# Weather_Station_v2_2-wihtparts.net
KiCad netlist of a schematic drawn in EAGLE
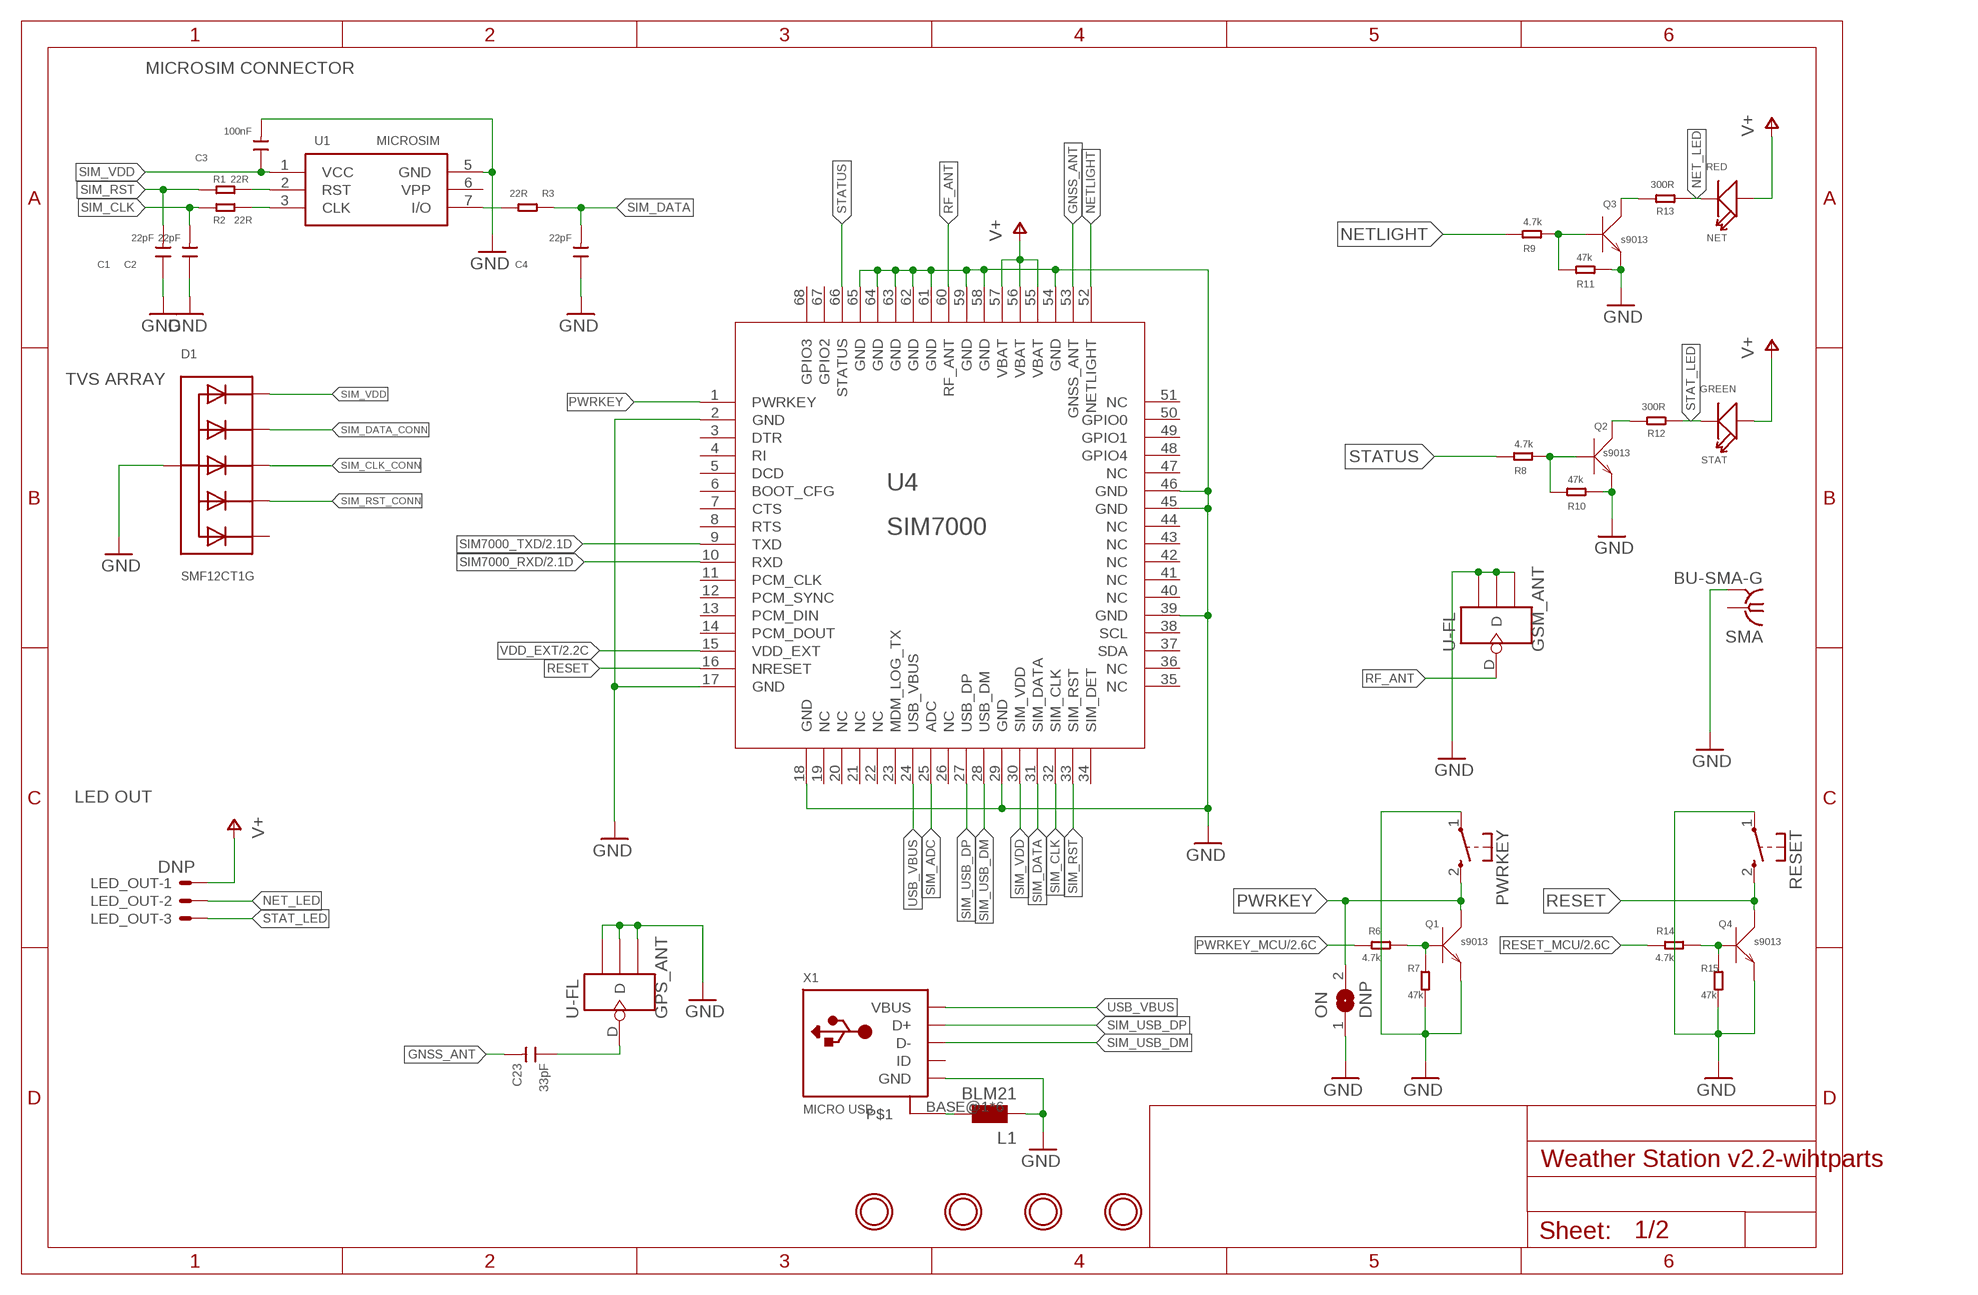
[diagram p0: schematic, sheet 1]
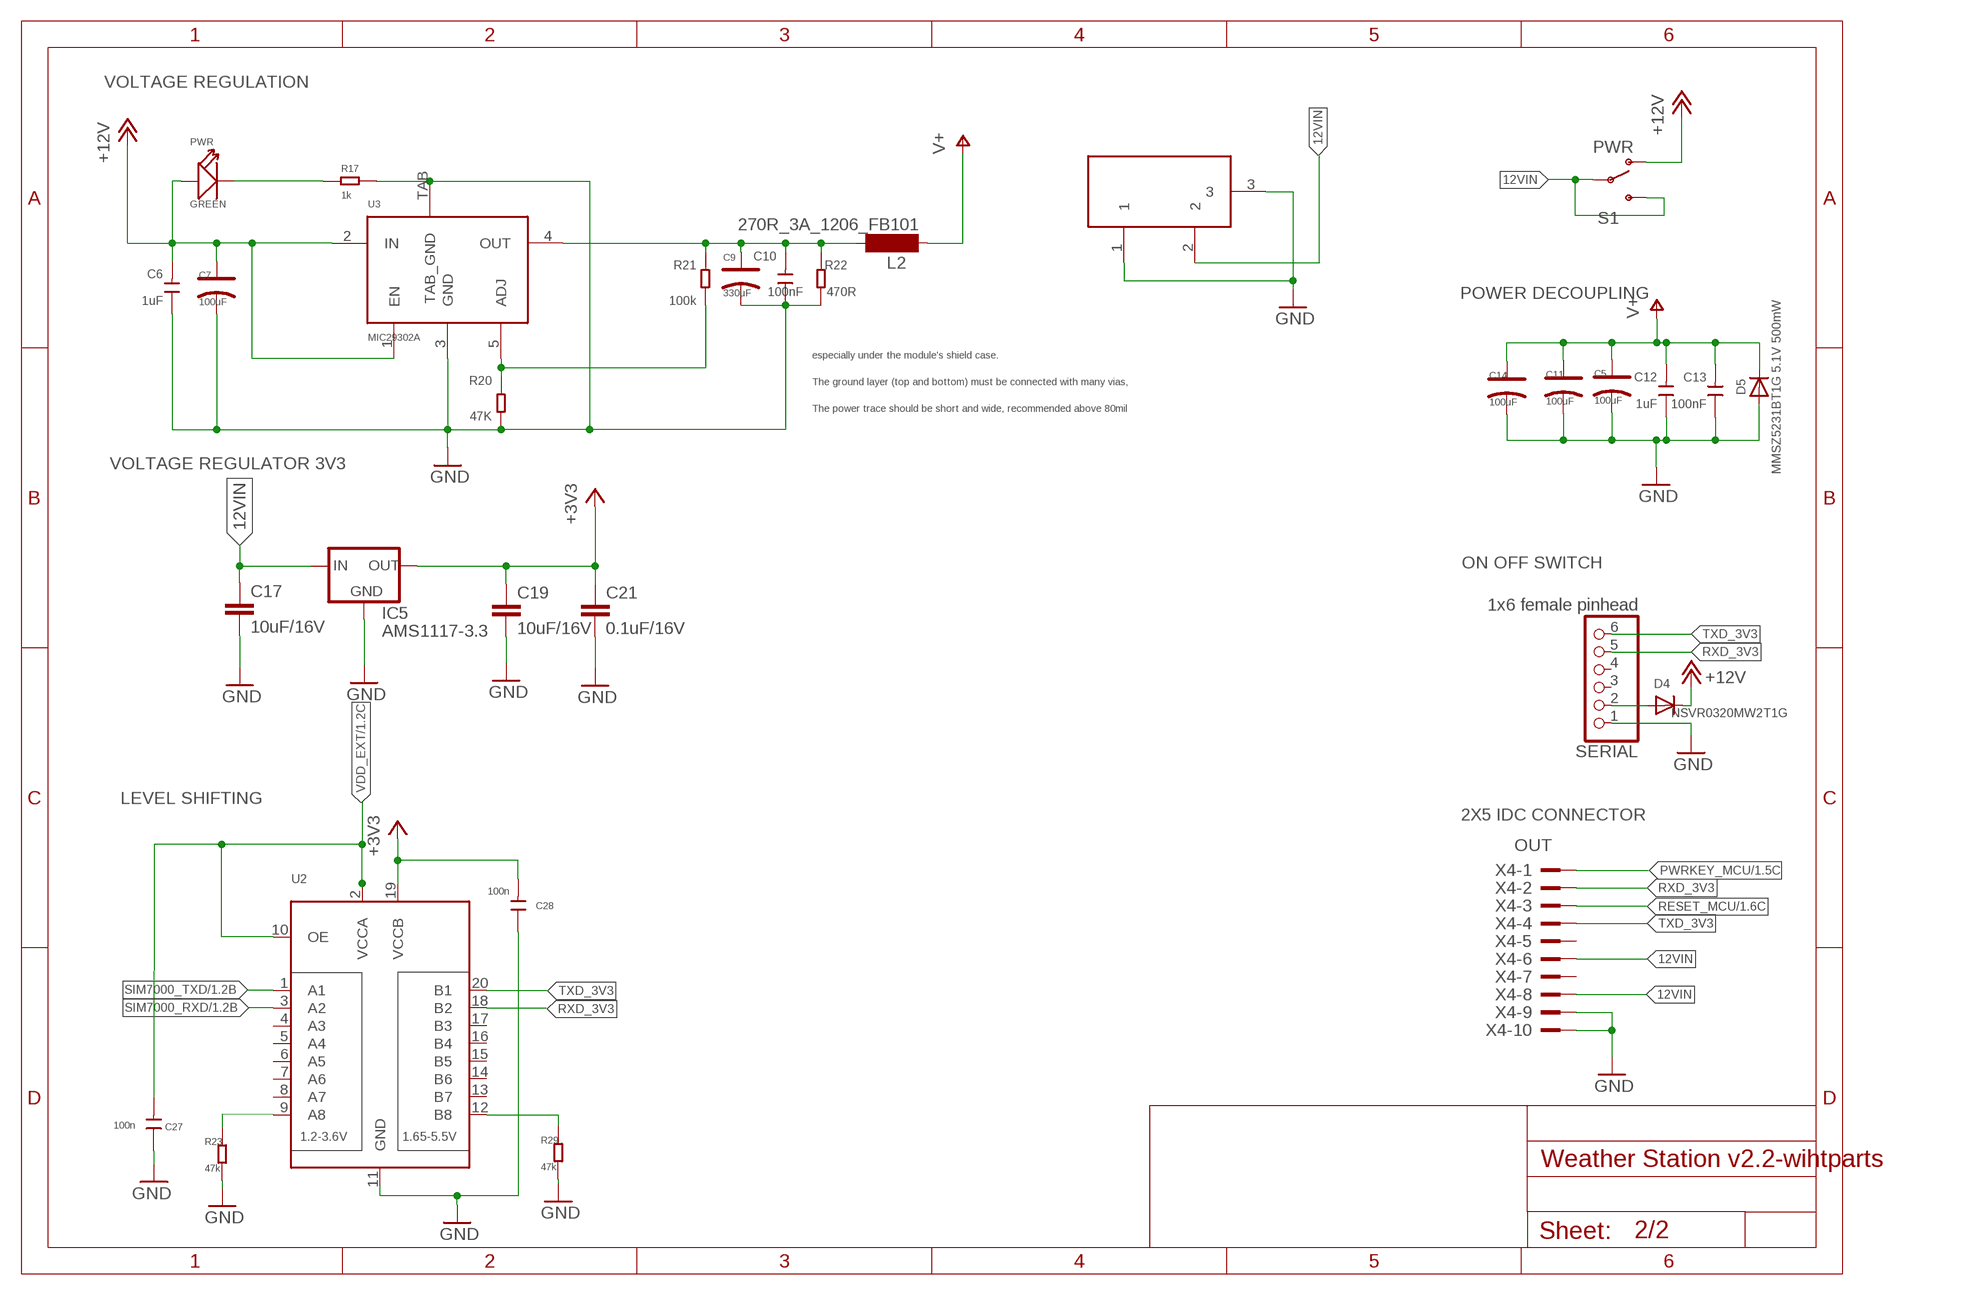
[diagram p1: schematic, sheet 2]

(export (version "E")
  (design (tool "Eeschema 10.0.6"))
  (components
    (comp (ref "C5")
      (value "100uF")
      (footprint "eagle-import:AVX_D")
      (fields (field (name "MPN") "TCJD107M025R0055"))
      (libsource (lib "eagle-import") (part "006-CAP_AVX_D"))
    )
    (comp (ref "C6")
      (value "1uF")
      (footprint "eagle-import:0805")
      (fields (field (name "MPN") "08053G105ZAT2A"))
      (libsource (lib "eagle-import") (part "C-0805"))
    )
    (comp (ref "C7")
      (value "100uF")
      (footprint "eagle-import:AVX_D")
      (fields (field (name "MPN") "TCJD107M025R0055"))
      (libsource (lib "eagle-import") (part "006-CAP_AVX_D"))
    )
    (comp (ref "C8")
      (value "DC21MMX")
      (footprint "eagle-import:DC-21MM")
      (fields (field (name "MPN") "FC681478"))
      (libsource (lib "eagle-import") (part "DC21MMX"))
    )
    (comp (ref "C9")
      (value "330uF")
      (footprint "eagle-import:AVX_D")
      (fields (field (name "MPN") "TCJE337M016R0050"))
      (libsource (lib "eagle-import") (part "006-CAP_AVX_D"))
    )
    (comp (ref "C10")
      (value "100nF")
      (footprint "eagle-import:0805")
      (fields (field (name "MPN") "MC0805B104M160CT"))
      (libsource (lib "eagle-import") (part "C-0805"))
    )
    (comp (ref "C11")
      (value "100uF")
      (footprint "eagle-import:AVX_D")
      (fields (field (name "MPN") "TCJD107M025R0055"))
      (libsource (lib "eagle-import") (part "006-CAP_AVX_D"))
    )
    (comp (ref "C12")
      (value "1uF")
      (footprint "eagle-import:0805")
      (fields (field (name "MPN") "GRM21BF51C106ZE15L"))
      (libsource (lib "eagle-import") (part "C-0805"))
    )
    (comp (ref "C13")
      (value "100nF")
      (footprint "eagle-import:0805")
      (fields (field (name "MPN") "08055A330JAT2A"))
      (libsource (lib "eagle-import") (part "C-0805"))
    )
    (comp (ref "C14")
      (value "100uF")
      (footprint "eagle-import:AVX_D")
      (fields (field (name "MPN") "TCJD107M025R0055"))
      (libsource (lib "eagle-import") (part "006-CAP_AVX_D"))
    )
    (comp (ref "C17")
      (value "10uF/16V")
      (footprint "eagle-import:C0805K")
      (libsource (lib "eagle-import") (part "C-EUC0805K"))
    )
    (comp (ref "C19")
      (value "10uF/16V")
      (footprint "eagle-import:C0805K")
      (libsource (lib "eagle-import") (part "C-EUC0805K"))
    )
    (comp (ref "C21")
      (value "0.1uF/16V")
      (footprint "eagle-import:C0805K")
      (libsource (lib "eagle-import") (part "C-EUC0805K"))
    )
    (comp (ref "C27")
      (value "100n")
      (footprint "eagle-import:0805")
      (libsource (lib "eagle-import") (part "C-0805"))
    )
    (comp (ref "C28")
      (value "100n")
      (footprint "eagle-import:0805")
      (libsource (lib "eagle-import") (part "C-0805"))
    )
    (comp (ref "D4")
      (value "NSVR0320MW2T1G")
      (footprint "eagle-import:SOD-323")
      (libsource (lib "eagle-import") (part "DIODESOD-323"))
    )
    (comp (ref "D5")
      (value "MMSZ5231BT1G 5.1V 500mW")
      (footprint "eagle-import:SOD-123")
      (fields (field (name "MF") "ON SEMICONDUCTOR") (field (name "MPN") "MMSZ5231BT1G"))
      (libsource (lib "eagle-import") (part "DIODESOD-123"))
    )
    (comp (ref "IC5")
      (value "AMS1117-3.3")
      (footprint "eagle-import:SOT223")
      (libsource (lib "eagle-import") (part "LM1117"))
    )
    (comp (ref "L2")
      (value "270R_3A_1206_FB101")
      (footprint "eagle-import:SM-1206")
      (fields (field (name "MPN") "742792121") (field (name "OC_NEWARK") "24AC5624"))
      (libsource (lib "eagle-import") (part "SM-1206"))
    )
    (comp (ref "PWR")
      (value "GREEN")
      (footprint "eagle-import:D0805")
      (fields (field (name "MPN") "SML-LX0805SUGC-TR"))
      (libsource (lib "eagle-import") (part "007-LED0805"))
    )
    (comp (ref "R17")
      (value "1k")
      (footprint "eagle-import:0805")
      (fields (field (name "MF") "VISHAY/DALE") (field (name "MPN") "CRCW08051K00FKTA"))
      (libsource (lib "eagle-import") (part "R-0805"))
    )
    (comp (ref "R20")
      (value "47K")
      (footprint "eagle-import:0805")
      (fields (field (name "MPN") "CRCW080543K0JNEA."))
      (libsource (lib "eagle-import") (part "R-0805"))
    )
    (comp (ref "R21")
      (value "100k")
      (footprint "eagle-import:0805")
      (fields (field (name "MPN") "CRCW0805100KJNEA"))
      (libsource (lib "eagle-import") (part "R-0805"))
    )
    (comp (ref "R22")
      (value "470R")
      (footprint "eagle-import:0805")
      (fields (field (name "MPN") "ERA-6AEB471V"))
      (libsource (lib "eagle-import") (part "R-0805"))
    )
    (comp (ref "R23")
      (value "47k")
      (footprint "eagle-import:0805")
      (libsource (lib "eagle-import") (part "R-0805"))
    )
    (comp (ref "R29")
      (value "47k")
      (footprint "eagle-import:0805")
      (libsource (lib "eagle-import") (part "R-0805"))
    )
    (comp (ref "S1")
      (value "PWR")
      (footprint "eagle-import:SWITCH-SPDT-CUSTOM")
      (fields (field (name "MPN") "EG1201"))
      (libsource (lib "eagle-import") (part "SWITCH-SPDT"))
    )
    (comp (ref "SERIAL")
      (value "1x6 female pinhead")
      (footprint "eagle-import:1X06")
      (libsource (lib "eagle-import") (part "PINHD-1X6"))
    )
    (comp (ref "U2")
      (value "TXB0108PWR")
      (footprint "eagle-import:TSSOP20")
      (libsource (lib "eagle-import") (part "TXB0108PWR"))
    )
    (comp (ref "U3")
      (value "MIC29302A")
      (footprint "eagle-import:TO-263A")
      (fields (field (name "MPN") "MIC29302WU-TR"))
      (libsource (lib "eagle-import") (part "MIC29302A"))
    )
    (comp (ref "X4")
      (value "OUT")
      (footprint "eagle-import:PAK100_2500-10")
      (fields
        (field (name "MF") "3M")
        (field (name "MPN") "2510-6002UB")
        (field (name "MPN_1") "30310-6002HB")
        (field (name "OC_NEWARK") "81H9257")
      )
      (libsource (lib "eagle-import") (part "2510-"))
    )
    (comp (ref "$H1")
      (value "DNP")
      (footprint "eagle-import:MOUNTINGHOLE_3.0_PLATEDTHIN")
      (libsource (lib "eagle-import") (part "MOUNTINGHOLE3.0THIN"))
    )
    (comp (ref "$H2")
      (value "DNP")
      (footprint "eagle-import:MOUNTINGHOLE_3.0_PLATEDTHIN")
      (libsource (lib "eagle-import") (part "MOUNTINGHOLE3.0THIN"))
    )
    (comp (ref "$H3")
      (value "DNP")
      (footprint "eagle-import:MOUNTINGHOLE_3.0_PLATEDTHIN")
      (libsource (lib "eagle-import") (part "MOUNTINGHOLE3.0THIN"))
    )
    (comp (ref "$H4")
      (value "DNP")
      (footprint "eagle-import:MOUNTINGHOLE_3.0_PLATEDTHIN")
      (libsource (lib "eagle-import") (part "MOUNTINGHOLE3.0THIN"))
    )
    (comp (ref "C1")
      (value "22pF")
      (footprint "eagle-import:0805")
      (fields (field (name "MF") "KEMET") (field (name "MPN") "C0402C220J5GACTU"))
      (libsource (lib "eagle-import") (part "C-0805"))
    )
    (comp (ref "C2")
      (value "22pF")
      (footprint "eagle-import:0805")
      (fields (field (name "MF") "KEMET") (field (name "MPN") "C0402C220J5GACTU"))
      (libsource (lib "eagle-import") (part "C-0805"))
    )
    (comp (ref "C3")
      (value "100nF")
      (footprint "eagle-import:0805")
      (fields (field (name "MPN") "08053G105ZAT2A"))
      (libsource (lib "eagle-import") (part "C-0805"))
    )
    (comp (ref "C4")
      (value "22pF")
      (footprint "eagle-import:0805")
      (fields (field (name "MF") "KEMET") (field (name "MPN") "C0402C220J5GACTU"))
      (libsource (lib "eagle-import") (part "C-0805"))
    )
    (comp (ref "C23")
      (value "33pF")
      (footprint "eagle-import:0805")
      (libsource (lib "eagle-import") (part "C-0805"))
    )
    (comp (ref "D1")
      (value "SMF12CT1G")
      (footprint "eagle-import:SOT363")
      (libsource (lib "eagle-import") (part "TVSARRAY_5LANE"))
    )
    (comp (ref "GPS_ANT")
      (value "U-FL")
      (footprint "eagle-import:4P-U-FL")
      (libsource (lib "eagle-import") (part "ANTENNA-U-FL"))
    )
    (comp (ref "GSM_ANT")
      (value "U-FL")
      (footprint "eagle-import:4P-U-FL")
      (fields (field (name "MF") "FARNELL") (field (name "MPN") "U.FL-R-SMT(01)"))
      (libsource (lib "eagle-import") (part "ANTENNA-U-FL"))
    )
    (comp (ref "L1")
      (value "BLM21")
      (footprint "eagle-import:0805")
      (fields (field (name "MPN") "BLM21AG121SN1D"))
      (libsource (lib "eagle-import") (part "WE-CBF_0805"))
    )
    (comp (ref "LED_OUT")
      (value "DNP")
      (footprint "eagle-import:JST-XH-03-WIRE")
      (fields (field (name "OC_NEWARK") "unknown"))
      (libsource (lib "eagle-import") (part "JST-XH-03-PIN"))
    )
    (comp (ref "NET")
      (value "RED")
      (footprint "eagle-import:LED-2P-2.54-3MM")
      (fields (field (name "MPN") "5988110107F"))
      (libsource (lib "eagle-import") (part "LED-3MM"))
    )
    (comp (ref "ON")
      (value "DNP")
      (footprint "eagle-import:SOLDERJUMPER_REFLOW")
      (libsource (lib "eagle-import") (part "SOLDERJUMPERREFLOW"))
    )
    (comp (ref "PWRKEY")
      (value "KSS-2EG4430")
      (footprint "eagle-import:KSS-2EG4430")
      (libsource (lib "eagle-import") (part "KSS-2EG4430"))
    )
    (comp (ref "Q1")
      (value "s9013")
      (footprint "eagle-import:SOT23")
      (fields (field (name "MPN") "DTC143TKAT146."))
      (libsource (lib "eagle-import") (part "TRANSISTOR-NPN-SOT23"))
    )
    (comp (ref "Q2")
      (value "s9013")
      (footprint "eagle-import:SOT23")
      (fields (field (name "MPN") "DTC143TKAT146."))
      (libsource (lib "eagle-import") (part "TRANSISTOR-NPN-SOT23"))
    )
    (comp (ref "Q3")
      (value "s9013")
      (footprint "eagle-import:SOT23")
      (fields (field (name "MPN") "DTC143TKAT146."))
      (libsource (lib "eagle-import") (part "TRANSISTOR-NPN-SOT23"))
    )
    (comp (ref "Q4")
      (value "s9013")
      (footprint "eagle-import:SOT23")
      (fields (field (name "MPN") "DTC143TKAT146."))
      (libsource (lib "eagle-import") (part "TRANSISTOR-NPN-SOT23"))
    )
    (comp (ref "R1")
      (value "22R")
      (footprint "eagle-import:0805")
      (fields (field (name "MPN") "CRM0805-FX-51R0ELF"))
      (libsource (lib "eagle-import") (part "R-0805"))
    )
    (comp (ref "R2")
      (value "22R")
      (footprint "eagle-import:0805")
      (fields (field (name "MPN") "CRM0805-FX-51R0ELF"))
      (libsource (lib "eagle-import") (part "R-0805"))
    )
    (comp (ref "R3")
      (value "22R")
      (footprint "eagle-import:0805")
      (fields (field (name "MPN") "CRM0805-FX-51R0ELF"))
      (libsource (lib "eagle-import") (part "R-0805"))
    )
    (comp (ref "R6")
      (value "4.7k")
      (footprint "eagle-import:0805")
      (fields (field (name "MPN") "MCWF08P4701FTL"))
      (libsource (lib "eagle-import") (part "R-0805"))
    )
    (comp (ref "R7")
      (value "47k")
      (footprint "eagle-import:0805")
      (fields (field (name "MF") "VISHAY/DALE") (field (name "MPN") "CRCW080547K0FKEA"))
      (libsource (lib "eagle-import") (part "R-0805"))
    )
    (comp (ref "R8")
      (value "4.7k")
      (footprint "eagle-import:0805")
      (fields (field (name "MPN") "MCWF08P4701FTL"))
      (libsource (lib "eagle-import") (part "R-0805"))
    )
    (comp (ref "R9")
      (value "4.7k")
      (footprint "eagle-import:0805")
      (fields (field (name "MPN") "MCWF08P4701FTL"))
      (libsource (lib "eagle-import") (part "R-0805"))
    )
    (comp (ref "R10")
      (value "47k")
      (footprint "eagle-import:0805")
      (fields (field (name "MF") "VISHAY/DALE") (field (name "MPN") "CRCW080547K0FKEA"))
      (libsource (lib "eagle-import") (part "R-0805"))
    )
    (comp (ref "R11")
      (value "47k")
      (footprint "eagle-import:0805")
      (fields (field (name "MF") "VISHAY/DALE") (field (name "MPN") "CRCW080547K0FKEA"))
      (libsource (lib "eagle-import") (part "R-0805"))
    )
    (comp (ref "R12")
      (value "300R")
      (footprint "eagle-import:0805")
      (fields (field (name "MPN") "ERA-6AEB301V"))
      (libsource (lib "eagle-import") (part "R-0805"))
    )
    (comp (ref "R13")
      (value "300R")
      (footprint "eagle-import:0805")
      (fields (field (name "MPN") "ERA-6AEB301V"))
      (libsource (lib "eagle-import") (part "R-0805"))
    )
    (comp (ref "R14")
      (value "4.7k")
      (footprint "eagle-import:0805")
      (fields (field (name "MPN") "MCWF08P4701FTL"))
      (libsource (lib "eagle-import") (part "R-0805"))
    )
    (comp (ref "R15")
      (value "47k")
      (footprint "eagle-import:0805")
      (fields (field (name "MF") "VISHAY/DALE") (field (name "MPN") "CRCW080547K0FKEA"))
      (libsource (lib "eagle-import") (part "R-0805"))
    )
    (comp (ref "RESET")
      (value "KSS-2EG4430")
      (footprint "eagle-import:KSS-2EG4430")
      (libsource (lib "eagle-import") (part "KSS-2EG4430"))
    )
    (comp (ref "SMA")
      (value "BU-SMA-G")
      (footprint "eagle-import:BU-SMA-G")
      (fields (field (name "MPN") "19-49-5-TGG") (field (name "OC_NEWARK") "26M6024"))
      (libsource (lib "eagle-import") (part "BU-SMA-G"))
    )
    (comp (ref "STAT")
      (value "GREEN")
      (footprint "eagle-import:LED-2P-2.54-3MM")
      (fields (field (name "MPN") "SML-LX0805SUGC-TR"))
      (libsource (lib "eagle-import") (part "LED-3MM"))
    )
    (comp (ref "U1")
      (value "MICROSIM")
      (footprint "eagle-import:MICROSIM")
      (libsource (lib "eagle-import") (part "MICROSIM"))
    )
    (comp (ref "U4")
      (value "SIM7000")
      (footprint "eagle-import:SIM7000")
      (libsource (lib "eagle-import") (part "SIM7000"))
    )
    (comp (ref "X1")
      (value "MICRO USB")
      (footprint "eagle-import:4UCONN_20329_V2")
      (fields (field (name "MPN") "10118193-0001LF"))
      (libsource (lib "eagle-import") (part "USB_MICRO_20329_V2"))
    )
  )
  (nets
    (net (code "1") (name "+3V3") (class "Default")
      (node (ref "C19") (pin "1") (pinfunction "1_1") (pintype "passive"))
      (node (ref "C21") (pin "1") (pinfunction "1_1") (pintype "passive"))
      (node (ref "C28") (pin "2") (pinfunction "2_2") (pintype "passive"))
      (node (ref "IC5") (pin "2") (pinfunction "OUT_2") (pintype "passive"))
      (node (ref "U2") (pin "19") (pinfunction "VCCB_19") (pintype "bidirectional"))
    )
    (net (code "2") (name "+12V") (class "Default")
      (node (ref "C6") (pin "2") (pinfunction "2_2") (pintype "passive"))
      (node (ref "C7") (pin "+") (pinfunction "+_+") (pintype "passive"))
      (node (ref "D4") (pin "C") (pinfunction "C_C") (pintype "passive"))
      (node (ref "PWR") (pin "+") (pinfunction "+_+") (pintype "passive"))
      (node (ref "S1") (pin "1") (pinfunction "O_1") (pintype "passive"))
      (node (ref "U3") (pin "1") (pinfunction "EN_1") (pintype "bidirectional"))
      (node (ref "U3") (pin "2") (pinfunction "IN_2") (pintype "bidirectional"))
    )
    (net (code "3") (name "12VIN") (class "Default")
      (node (ref "C17") (pin "1") (pinfunction "1_1") (pintype "passive"))
      (node (ref "C8") (pin "2") (pinfunction "2_2") (pintype "power_in"))
      (node (ref "IC5") (pin "3") (pinfunction "IN_3") (pintype "input"))
      (node (ref "S1") (pin "2") (pinfunction "P_2") (pintype "passive"))
      (node (ref "S1") (pin "3") (pinfunction "S_3") (pintype "passive"))
      (node (ref "X4") (pin "6") (pinfunction "KL_6") (pintype "passive"))
      (node (ref "X4") (pin "8") (pinfunction "KL_8") (pintype "passive"))
    )
    (net (code "4") (name "GND") (class "Default")
      (node (ref "C1") (pin "1") (pinfunction "1_1") (pintype "passive"))
      (node (ref "C10") (pin "1") (pinfunction "1_1") (pintype "passive"))
      (node (ref "C11") (pin "-") (pinfunction "-_-") (pintype "passive"))
      (node (ref "C12") (pin "1") (pinfunction "1_1") (pintype "passive"))
      (node (ref "C13") (pin "1") (pinfunction "1_1") (pintype "passive"))
      (node (ref "C14") (pin "-") (pinfunction "-_-") (pintype "passive"))
      (node (ref "C17") (pin "2") (pinfunction "2_2") (pintype "passive"))
      (node (ref "C19") (pin "2") (pinfunction "2_2") (pintype "passive"))
      (node (ref "C2") (pin "1") (pinfunction "1_1") (pintype "passive"))
      (node (ref "C21") (pin "2") (pinfunction "2_2") (pintype "passive"))
      (node (ref "C27") (pin "1") (pinfunction "1_1") (pintype "passive"))
      (node (ref "C28") (pin "1") (pinfunction "1_1") (pintype "passive"))
      (node (ref "C3") (pin "2") (pinfunction "2_2") (pintype "passive"))
      (node (ref "C4") (pin "1") (pinfunction "1_1") (pintype "passive"))
      (node (ref "C5") (pin "-") (pinfunction "-_-") (pintype "passive"))
      (node (ref "C6") (pin "1") (pinfunction "1_1") (pintype "passive"))
      (node (ref "C7") (pin "-") (pinfunction "-_-") (pintype "passive"))
      (node (ref "C8") (pin "1") (pinfunction "1_1") (pintype "power_in"))
      (node (ref "C8") (pin "3") (pinfunction "3_3") (pintype "power_in"))
      (node (ref "C9") (pin "-") (pinfunction "-_-") (pintype "passive"))
      (node (ref "D1") (pin "2") (pinfunction "A_2") (pintype "passive"))
      (node (ref "D5") (pin "A") (pinfunction "A_A") (pintype "passive"))
      (node (ref "GPS_ANT") (pin "GND1") (pinfunction "GND1_GND1") (pintype "bidirectional"))
      (node (ref "GPS_ANT") (pin "GND2") (pinfunction "GND2_GND2") (pintype "bidirectional"))
      (node (ref "GPS_ANT") (pin "GND3") (pinfunction "GND3_GND3") (pintype "bidirectional"))
      (node (ref "GSM_ANT") (pin "GND1") (pinfunction "GND1_GND1") (pintype "bidirectional"))
      (node (ref "GSM_ANT") (pin "GND2") (pinfunction "GND2_GND2") (pintype "bidirectional"))
      (node (ref "GSM_ANT") (pin "GND3") (pinfunction "GND3_GND3") (pintype "bidirectional"))
      (node (ref "IC5") (pin "1") (pinfunction "GND_1") (pintype "input"))
      (node (ref "L1") (pin "1") (pinfunction "1_1") (pintype "passive"))
      (node (ref "ON") (pin "1") (pinfunction "1_1") (pintype "passive"))
      (node (ref "PWRKEY") (pin "1") (pinfunction "P_1") (pintype "passive"))
      (node (ref "Q1") (pin "2") (pinfunction "E_2") (pintype "passive"))
      (node (ref "Q2") (pin "2") (pinfunction "E_2") (pintype "passive"))
      (node (ref "Q3") (pin "2") (pinfunction "E_2") (pintype "passive"))
      (node (ref "Q4") (pin "2") (pinfunction "E_2") (pintype "passive"))
      (node (ref "R10") (pin "2") (pinfunction "2_2") (pintype "passive"))
      (node (ref "R11") (pin "2") (pinfunction "2_2") (pintype "passive"))
      (node (ref "R15") (pin "2") (pinfunction "2_2") (pintype "passive"))
      (node (ref "R17") (pin "2") (pinfunction "2_2") (pintype "passive"))
      (node (ref "R20") (pin "1") (pinfunction "1_1") (pintype "passive"))
      (node (ref "R22") (pin "1") (pinfunction "1_1") (pintype "passive"))
      (node (ref "R23") (pin "2") (pinfunction "2_2") (pintype "passive"))
      (node (ref "R29") (pin "2") (pinfunction "2_2") (pintype "passive"))
      (node (ref "R7") (pin "2") (pinfunction "2_2") (pintype "passive"))
      (node (ref "RESET") (pin "1") (pinfunction "P_1") (pintype "passive"))
      (node (ref "SERIAL") (pin "1") (pinfunction "1_1") (pintype "passive"))
      (node (ref "SMA") (pin "2") (pinfunction "2_2") (pintype "passive"))
      (node (ref "SMA") (pin "3") (pinfunction "2_3") (pintype "passive"))
      (node (ref "SMA") (pin "4") (pinfunction "2_4") (pintype "passive"))
      (node (ref "SMA") (pin "5") (pinfunction "2_5") (pintype "passive"))
      (node (ref "U1") (pin "5") (pinfunction "GND_5") (pintype "bidirectional"))
      (node (ref "U2") (pin "11") (pinfunction "GND_11") (pintype "bidirectional"))
      (node (ref "U3") (pin "3") (pinfunction "GND_3") (pintype "bidirectional"))
      (node (ref "U3") (pin "TAB") (pinfunction "TAB_GND_TAB") (pintype "bidirectional"))
      (node (ref "U4") (pin "17") (pinfunction "GND_17") (pintype "power_in"))
      (node (ref "U4") (pin "18") (pinfunction "GND_18") (pintype "power_in"))
      (node (ref "U4") (pin "2") (pinfunction "GND_2") (pintype "power_in"))
      (node (ref "U4") (pin "29") (pinfunction "GND_29") (pintype "power_in"))
      (node (ref "U4") (pin "39") (pinfunction "GND_39") (pintype "power_in"))
      (node (ref "U4") (pin "45") (pinfunction "GND_45") (pintype "power_in"))
      (node (ref "U4") (pin "46") (pinfunction "GND_46") (pintype "power_in"))
      (node (ref "U4") (pin "54") (pinfunction "GND_54") (pintype "power_in"))
      (node (ref "U4") (pin "58") (pinfunction "GND_58") (pintype "output"))
      (node (ref "U4") (pin "59") (pinfunction "GND_59") (pintype "bidirectional"))
      (node (ref "U4") (pin "61") (pinfunction "GND_61") (pintype "input"))
      (node (ref "U4") (pin "62") (pinfunction "GND_62") (pintype "output"))
      (node (ref "U4") (pin "63") (pinfunction "GND_63") (pintype "output"))
      (node (ref "U4") (pin "64") (pinfunction "GND_64") (pintype "input"))
      (node (ref "U4") (pin "65") (pinfunction "GND_65") (pintype "bidirectional"))
      (node (ref "X1") (pin "GND") (pinfunction "GND_GND") (pintype "power_in"))
      (node (ref "X4") (pin "10") (pinfunction "KL_10") (pintype "passive"))
      (node (ref "X4") (pin "9") (pinfunction "KL_9") (pintype "passive"))
    )
    (net (code "5") (name "GNSS_ANT") (class "Default")
      (node (ref "C23") (pin "2") (pinfunction "2_2") (pintype "passive"))
      (node (ref "U4") (pin "53") (pinfunction "GNSS_ANT_53") (pintype "power_in"))
    )
    (net (code "6") (name "GPIO2") (class "Default")
      (node (ref "U4") (pin "67") (pinfunction "GPIO2_67") (pintype "power_in"))
    )
    (net (code "7") (name "GPIO3") (class "Default")
      (node (ref "U4") (pin "68") (pinfunction "GPIO3_68") (pintype "power_in"))
    )
    (net (code "8") (name "NETLIGHT") (class "Default")
      (node (ref "R9") (pin "1") (pinfunction "1_1") (pintype "passive"))
      (node (ref "U4") (pin "52") (pinfunction "NETLIGHT_52") (pintype "power_in"))
    )
    (net (code "9") (name "NET_LED") (class "Default")
      (node (ref "LED_OUT") (pin "2") (pinfunction "S_2") (pintype "passive"))
      (node (ref "NET") (pin "K") (pinfunction "-_K") (pintype "passive"))
      (node (ref "R13") (pin "1") (pinfunction "1_1") (pintype "passive"))
    )
    (net (code "10") (name "Net-(C23-Pad1)") (class "Default")
      (node (ref "C23") (pin "1") (pinfunction "1_1") (pintype "passive"))
      (node (ref "GPS_ANT") (pin "D") (pinfunction "D_D") (pintype "bidirectional"))
    )
    (net (code "11") (name "Net-(D4-PadA)") (class "Default")
      (node (ref "D4") (pin "A") (pinfunction "A_A") (pintype "passive"))
      (node (ref "SERIAL") (pin "2") (pinfunction "2_2") (pintype "passive"))
    )
    (net (code "12") (name "Net-(L1-Pad2)") (class "Default")
      (node (ref "L1") (pin "2") (pinfunction "2_2") (pintype "passive"))
      (node (ref "X1") (pin "BASE@1") (pinfunction "P$1_BASE@1") (pintype "bidirectional"))
      (node (ref "X1") (pin "BASE@2") (pinfunction "P$1_BASE@2") (pintype "bidirectional"))
      (node (ref "X1") (pin "SPRT@1") (pinfunction "P$1_SPRT@1") (pintype "bidirectional"))
      (node (ref "X1") (pin "SPRT@2") (pinfunction "P$1_SPRT@2") (pintype "bidirectional"))
      (node (ref "X1") (pin "SPRT@3") (pinfunction "P$1_SPRT@3") (pintype "bidirectional"))
      (node (ref "X1") (pin "SPRT@4") (pinfunction "P$1_SPRT@4") (pintype "bidirectional"))
    )
    (net (code "13") (name "Net-(PWR-Pad-)") (class "Default")
      (node (ref "PWR") (pin "-") (pinfunction "-_-") (pintype "passive"))
      (node (ref "R17") (pin "1") (pinfunction "1_1") (pintype "passive"))
    )
    (net (code "14") (name "Net-(Q1-B)") (class "Default")
      (node (ref "Q1") (pin "1") (pinfunction "B_1") (pintype "passive"))
      (node (ref "R6") (pin "2") (pinfunction "2_2") (pintype "passive"))
      (node (ref "R7") (pin "1") (pinfunction "1_1") (pintype "passive"))
    )
    (net (code "15") (name "Net-(Q2-B)") (class "Default")
      (node (ref "Q2") (pin "1") (pinfunction "B_1") (pintype "passive"))
      (node (ref "R10") (pin "1") (pinfunction "1_1") (pintype "passive"))
      (node (ref "R8") (pin "2") (pinfunction "2_2") (pintype "passive"))
    )
    (net (code "16") (name "Net-(Q2-C)") (class "Default")
      (node (ref "Q2") (pin "3") (pinfunction "C_3") (pintype "passive"))
      (node (ref "R12") (pin "2") (pinfunction "2_2") (pintype "passive"))
    )
    (net (code "17") (name "Net-(Q3-B)") (class "Default")
      (node (ref "Q3") (pin "1") (pinfunction "B_1") (pintype "passive"))
      (node (ref "R11") (pin "1") (pinfunction "1_1") (pintype "passive"))
      (node (ref "R9") (pin "2") (pinfunction "2_2") (pintype "passive"))
    )
    (net (code "18") (name "Net-(Q3-C)") (class "Default")
      (node (ref "Q3") (pin "3") (pinfunction "C_3") (pintype "passive"))
      (node (ref "R13") (pin "2") (pinfunction "2_2") (pintype "passive"))
    )
    (net (code "19") (name "Net-(Q4-B)") (class "Default")
      (node (ref "Q4") (pin "1") (pinfunction "B_1") (pintype "passive"))
      (node (ref "R14") (pin "2") (pinfunction "2_2") (pintype "passive"))
      (node (ref "R15") (pin "1") (pinfunction "1_1") (pintype "passive"))
    )
    (net (code "20") (name "Net-(U2-A8)") (class "Default")
      (node (ref "R23") (pin "1") (pinfunction "1_1") (pintype "passive"))
      (node (ref "U2") (pin "9") (pinfunction "A8_9") (pintype "bidirectional"))
    )
    (net (code "21") (name "Net-(U2-B8)") (class "Default")
      (node (ref "R29") (pin "1") (pinfunction "1_1") (pintype "passive"))
      (node (ref "U2") (pin "12") (pinfunction "B8_12") (pintype "bidirectional"))
    )
    (net (code "22") (name "Net-(U3-ADJ)") (class "Default")
      (node (ref "R20") (pin "2") (pinfunction "2_2") (pintype "passive"))
      (node (ref "R21") (pin "1") (pinfunction "1_1") (pintype "passive"))
      (node (ref "U3") (pin "5") (pinfunction "ADJ_5") (pintype "bidirectional"))
    )
    (net (code "23") (name "Net-(U3-OUT)") (class "Default")
      (node (ref "C10") (pin "2") (pinfunction "2_2") (pintype "passive"))
      (node (ref "C9") (pin "+") (pinfunction "+_+") (pintype "passive"))
      (node (ref "L2") (pin "2") (pinfunction "2_2") (pintype "passive"))
      (node (ref "R21") (pin "2") (pinfunction "2_2") (pintype "passive"))
      (node (ref "R22") (pin "2") (pinfunction "2_2") (pintype "passive"))
      (node (ref "U3") (pin "4") (pinfunction "OUT_4") (pintype "bidirectional"))
    )
    (net (code "24") (name "PWRKEY") (class "Default")
      (node (ref "ON") (pin "2") (pinfunction "2_2") (pintype "passive"))
      (node (ref "PWRKEY") (pin "2") (pinfunction "S_2") (pintype "passive"))
      (node (ref "Q1") (pin "3") (pinfunction "C_3") (pintype "passive"))
      (node (ref "U4") (pin "1") (pinfunction "PWRKEY_1") (pintype "input"))
    )
    (net (code "25") (name "PWRKEY_MCU") (class "Default")
      (node (ref "R6") (pin "1") (pinfunction "1_1") (pintype "passive"))
      (node (ref "X4") (pin "1") (pinfunction "KL_1") (pintype "passive"))
    )
    (net (code "26") (name "RESET") (class "Default")
      (node (ref "Q4") (pin "3") (pinfunction "C_3") (pintype "passive"))
      (node (ref "RESET") (pin "2") (pinfunction "S_2") (pintype "passive"))
      (node (ref "U4") (pin "16") (pinfunction "NRESET_16") (pintype "input"))
    )
    (net (code "27") (name "RESET_MCU") (class "Default")
      (node (ref "R14") (pin "1") (pinfunction "1_1") (pintype "passive"))
      (node (ref "X4") (pin "3") (pinfunction "KL_3") (pintype "passive"))
    )
    (net (code "28") (name "RF_ANT") (class "Default")
      (node (ref "GSM_ANT") (pin "D") (pinfunction "D_D") (pintype "bidirectional"))
      (node (ref "U4") (pin "60") (pinfunction "RF_ANT_60") (pintype "power_in"))
    )
    (net (code "29") (name "RXD_3V3") (class "Default")
      (node (ref "SERIAL") (pin "5") (pinfunction "5_5") (pintype "passive"))
      (node (ref "U2") (pin "18") (pinfunction "B2_18") (pintype "bidirectional"))
      (node (ref "X4") (pin "2") (pinfunction "KL_2") (pintype "passive"))
    )
    (net (code "30") (name "SIM7000_RXD") (class "Default")
      (node (ref "U2") (pin "3") (pinfunction "A2_3") (pintype "bidirectional"))
      (node (ref "U4") (pin "10") (pinfunction "RXD_10") (pintype "input"))
    )
    (net (code "31") (name "SIM7000_TXD") (class "Default")
      (node (ref "U2") (pin "1") (pinfunction "A1_1") (pintype "bidirectional"))
      (node (ref "U4") (pin "9") (pinfunction "TXD_9") (pintype "output"))
    )
    (net (code "32") (name "SIM_ADC") (class "Default")
      (node (ref "U4") (pin "25") (pinfunction "ADC_25") (pintype "input"))
    )
    (net (code "33") (name "SIM_CLK") (class "Default")
      (node (ref "C2") (pin "2") (pinfunction "2_2") (pintype "passive"))
      (node (ref "R2") (pin "2") (pinfunction "2_2") (pintype "passive"))
      (node (ref "U4") (pin "32") (pinfunction "SIM_CLK_32") (pintype "output"))
    )
    (net (code "34") (name "SIM_CLK_CONN") (class "Default")
      (node (ref "D1") (pin "4") (pinfunction "C3_4") (pintype "passive"))
      (node (ref "R2") (pin "1") (pinfunction "1_1") (pintype "passive"))
      (node (ref "U1") (pin "3") (pinfunction "CLK_3") (pintype "bidirectional"))
    )
    (net (code "35") (name "SIM_DATA") (class "Default")
      (node (ref "C4") (pin "2") (pinfunction "2_2") (pintype "passive"))
      (node (ref "R3") (pin "1") (pinfunction "1_1") (pintype "passive"))
      (node (ref "U4") (pin "31") (pinfunction "SIM_DATA_31") (pintype "output"))
    )
    (net (code "36") (name "SIM_DATA_CONN") (class "Default")
      (node (ref "D1") (pin "3") (pinfunction "C2_3") (pintype "passive"))
      (node (ref "R3") (pin "2") (pinfunction "2_2") (pintype "passive"))
      (node (ref "U1") (pin "7") (pinfunction "I/O_7") (pintype "bidirectional"))
    )
    (net (code "37") (name "SIM_RST") (class "Default")
      (node (ref "C1") (pin "2") (pinfunction "2_2") (pintype "passive"))
      (node (ref "R1") (pin "2") (pinfunction "2_2") (pintype "passive"))
      (node (ref "U4") (pin "33") (pinfunction "SIM_RST_33") (pintype "bidirectional"))
    )
    (net (code "38") (name "SIM_RST_CONN") (class "Default")
      (node (ref "D1") (pin "5") (pinfunction "C4_5") (pintype "passive"))
      (node (ref "R1") (pin "1") (pinfunction "1_1") (pintype "passive"))
      (node (ref "U1") (pin "2") (pinfunction "RST_2") (pintype "bidirectional"))
    )
    (net (code "39") (name "SIM_USB_DM") (class "Default")
      (node (ref "U4") (pin "28") (pinfunction "USB_DM_28") (pintype "output"))
      (node (ref "X1") (pin "D-") (pinfunction "D-_D-") (pintype "bidirectional"))
    )
    (net (code "40") (name "SIM_USB_DP") (class "Default")
      (node (ref "U4") (pin "27") (pinfunction "USB_DP_27") (pintype "bidirectional"))
      (node (ref "X1") (pin "D+") (pinfunction "D+_D+") (pintype "bidirectional"))
    )
    (net (code "41") (name "SIM_VDD") (class "Default")
      (node (ref "C3") (pin "1") (pinfunction "1_1") (pintype "passive"))
      (node (ref "D1") (pin "1") (pinfunction "C1_1") (pintype "passive"))
      (node (ref "U1") (pin "1") (pinfunction "VCC_1") (pintype "bidirectional"))
      (node (ref "U4") (pin "30") (pinfunction "SIM_VDD_30") (pintype "input"))
    )
    (net (code "42") (name "STATUS") (class "Default")
      (node (ref "R8") (pin "1") (pinfunction "1_1") (pintype "passive"))
      (node (ref "U4") (pin "66") (pinfunction "STATUS_66") (pintype "power_in"))
    )
    (net (code "43") (name "STAT_LED") (class "Default")
      (node (ref "LED_OUT") (pin "3") (pinfunction "S_3") (pintype "passive"))
      (node (ref "R12") (pin "1") (pinfunction "1_1") (pintype "passive"))
      (node (ref "STAT") (pin "K") (pinfunction "-_K") (pintype "passive"))
    )
    (net (code "44") (name "TXD_3V3") (class "Default")
      (node (ref "SERIAL") (pin "6") (pinfunction "6_6") (pintype "passive"))
      (node (ref "U2") (pin "20") (pinfunction "B1_20") (pintype "bidirectional"))
      (node (ref "X4") (pin "4") (pinfunction "KL_4") (pintype "passive"))
    )
    (net (code "45") (name "USB_VBUS") (class "Default")
      (node (ref "U4") (pin "24") (pinfunction "USB_VBUS_24") (pintype "output"))
      (node (ref "X1") (pin "VBUS") (pinfunction "VBUS_VBUS") (pintype "power_in"))
    )
    (net (code "46") (name "V+") (class "Default")
      (node (ref "C11") (pin "+") (pinfunction "+_+") (pintype "passive"))
      (node (ref "C12") (pin "2") (pinfunction "2_2") (pintype "passive"))
      (node (ref "C13") (pin "2") (pinfunction "2_2") (pintype "passive"))
      (node (ref "C14") (pin "+") (pinfunction "+_+") (pintype "passive"))
      (node (ref "C5") (pin "+") (pinfunction "+_+") (pintype "passive"))
      (node (ref "D5") (pin "C") (pinfunction "C_C") (pintype "passive"))
      (node (ref "L2") (pin "1") (pinfunction "1_1") (pintype "passive"))
      (node (ref "LED_OUT") (pin "1") (pinfunction "S_1") (pintype "passive"))
      (node (ref "NET") (pin "A") (pinfunction "+_A") (pintype "passive"))
      (node (ref "STAT") (pin "A") (pinfunction "+_A") (pintype "passive"))
      (node (ref "U4") (pin "55") (pinfunction "VBAT_55") (pintype "power_in"))
      (node (ref "U4") (pin "56") (pinfunction "VBAT_56") (pintype "power_in"))
      (node (ref "U4") (pin "57") (pinfunction "VBAT_57") (pintype "power_in"))
    )
    (net (code "47") (name "VDD_EXT") (class "Default")
      (node (ref "C27") (pin "2") (pinfunction "2_2") (pintype "passive"))
      (node (ref "U2") (pin "10") (pinfunction "OE_10") (pintype "bidirectional"))
      (node (ref "U2") (pin "2") (pinfunction "VCCA_2") (pintype "bidirectional"))
      (node (ref "U4") (pin "15") (pinfunction "VDD_EXT_15") (pintype "output"))
    )
    (net (code "48") (name "unconnected-(D1-C5-Pad6)") (class "Default")
      (node (ref "D1") (pin "6") (pinfunction "C5_6") (pintype "passive"))
    )
    (net (code "49") (name "unconnected-(SERIAL-Pad3)") (class "Default")
      (node (ref "SERIAL") (pin "3") (pinfunction "3_3") (pintype "passive"))
    )
    (net (code "50") (name "unconnected-(SERIAL-Pad4)") (class "Default")
      (node (ref "SERIAL") (pin "4") (pinfunction "4_4") (pintype "passive"))
    )
    (net (code "51") (name "unconnected-(SMA-Pad1)") (class "Default")
      (node (ref "SMA") (pin "1") (pinfunction "1_1") (pintype "passive"))
    )
    (net (code "52") (name "unconnected-(U1-VPP-Pad6)") (class "Default")
      (node (ref "U1") (pin "6") (pinfunction "VPP_6") (pintype "bidirectional"))
    )
    (net (code "53") (name "unconnected-(U2-A3-Pad4)") (class "Default")
      (node (ref "U2") (pin "4") (pinfunction "A3_4") (pintype "bidirectional"))
    )
    (net (code "54") (name "unconnected-(U2-A4-Pad5)") (class "Default")
      (node (ref "U2") (pin "5") (pinfunction "A4_5") (pintype "bidirectional"))
    )
    (net (code "55") (name "unconnected-(U2-A5-Pad6)") (class "Default")
      (node (ref "U2") (pin "6") (pinfunction "A5_6") (pintype "bidirectional"))
    )
    (net (code "56") (name "unconnected-(U2-A6-Pad7)") (class "Default")
      (node (ref "U2") (pin "7") (pinfunction "A6_7") (pintype "bidirectional"))
    )
    (net (code "57") (name "unconnected-(U2-A7-Pad8)") (class "Default")
      (node (ref "U2") (pin "8") (pinfunction "A7_8") (pintype "bidirectional"))
    )
    (net (code "58") (name "unconnected-(U2-B3-Pad17)") (class "Default")
      (node (ref "U2") (pin "17") (pinfunction "B3_17") (pintype "bidirectional"))
    )
    (net (code "59") (name "unconnected-(U2-B4-Pad16)") (class "Default")
      (node (ref "U2") (pin "16") (pinfunction "B4_16") (pintype "bidirectional"))
    )
    (net (code "60") (name "unconnected-(U2-B5-Pad15)") (class "Default")
      (node (ref "U2") (pin "15") (pinfunction "B5_15") (pintype "bidirectional"))
    )
    (net (code "61") (name "unconnected-(U2-B6-Pad14)") (class "Default")
      (node (ref "U2") (pin "14") (pinfunction "B6_14") (pintype "bidirectional"))
    )
    (net (code "62") (name "unconnected-(U2-B7-Pad13)") (class "Default")
      (node (ref "U2") (pin "13") (pinfunction "B7_13") (pintype "bidirectional"))
    )
    (net (code "63") (name "unconnected-(U4-BOOT_CFG-Pad6)") (class "Default")
      (node (ref "U4") (pin "6") (pinfunction "BOOT_CFG_6") (pintype "output"))
    )
    (net (code "64") (name "unconnected-(U4-CTS-Pad7)") (class "Default")
      (node (ref "U4") (pin "7") (pinfunction "CTS_7") (pintype "output"))
    )
    (net (code "65") (name "unconnected-(U4-DCD-Pad5)") (class "Default")
      (node (ref "U4") (pin "5") (pinfunction "DCD_5") (pintype "output"))
    )
    (net (code "66") (name "unconnected-(U4-DTR-Pad3)") (class "Default")
      (node (ref "U4") (pin "3") (pinfunction "DTR_3") (pintype "input"))
    )
    (net (code "67") (name "unconnected-(U4-GPIO0-Pad50)") (class "Default")
      (node (ref "U4") (pin "50") (pinfunction "GPIO0_50") (pintype "bidirectional"))
    )
    (net (code "68") (name "unconnected-(U4-GPIO1-Pad49)") (class "Default")
      (node (ref "U4") (pin "49") (pinfunction "GPIO1_49") (pintype "bidirectional"))
    )
    (net (code "69") (name "unconnected-(U4-GPIO4-Pad48)") (class "Default")
      (node (ref "U4") (pin "48") (pinfunction "GPIO4_48") (pintype "input"))
    )
    (net (code "70") (name "unconnected-(U4-MDM_LOG_TX-Pad23)") (class "Default")
      (node (ref "U4") (pin "23") (pinfunction "MDM_LOG_TX_23") (pintype "input"))
    )
    (net (code "71") (name "unconnected-(U4-NC-Pad19)") (class "Default")
      (node (ref "U4") (pin "19") (pinfunction "NC_19") (pintype "input"))
    )
    (net (code "72") (name "unconnected-(U4-NC-Pad20)") (class "Default")
      (node (ref "U4") (pin "20") (pinfunction "NC_20") (pintype "output"))
    )
    (net (code "73") (name "unconnected-(U4-NC-Pad21)") (class "Default")
      (node (ref "U4") (pin "21") (pinfunction "NC_21") (pintype "output"))
    )
    (net (code "74") (name "unconnected-(U4-NC-Pad22)") (class "Default")
      (node (ref "U4") (pin "22") (pinfunction "NC_22") (pintype "input"))
    )
    (net (code "75") (name "unconnected-(U4-NC-Pad26)") (class "Default")
      (node (ref "U4") (pin "26") (pinfunction "NC_26") (pintype "output"))
    )
    (net (code "76") (name "unconnected-(U4-NC-Pad35)") (class "Default")
      (node (ref "U4") (pin "35") (pinfunction "NC_35") (pintype "input"))
    )
    (net (code "77") (name "unconnected-(U4-NC-Pad36)") (class "Default")
      (node (ref "U4") (pin "36") (pinfunction "NC_36") (pintype "output"))
    )
    (net (code "78") (name "unconnected-(U4-NC-Pad40)") (class "Default")
      (node (ref "U4") (pin "40") (pinfunction "NC_40") (pintype "output"))
    )
    (net (code "79") (name "unconnected-(U4-NC-Pad41)") (class "Default")
      (node (ref "U4") (pin "41") (pinfunction "NC_41") (pintype "output"))
    )
    (net (code "80") (name "unconnected-(U4-NC-Pad42)") (class "Default")
      (node (ref "U4") (pin "42") (pinfunction "NC_42") (pintype "output"))
    )
    (net (code "81") (name "unconnected-(U4-NC-Pad43)") (class "Default")
      (node (ref "U4") (pin "43") (pinfunction "NC_43") (pintype "output"))
    )
    (net (code "82") (name "unconnected-(U4-NC-Pad44)") (class "Default")
      (node (ref "U4") (pin "44") (pinfunction "NC_44") (pintype "output"))
    )
    (net (code "83") (name "unconnected-(U4-NC-Pad47)") (class "Default")
      (node (ref "U4") (pin "47") (pinfunction "NC_47") (pintype "input"))
    )
    (net (code "84") (name "unconnected-(U4-NC-Pad51)") (class "Default")
      (node (ref "U4") (pin "51") (pinfunction "NC_51") (pintype "bidirectional"))
    )
    (net (code "85") (name "unconnected-(U4-PCM_CLK-Pad11)") (class "Default")
      (node (ref "U4") (pin "11") (pinfunction "PCM_CLK_11") (pintype "output"))
    )
    (net (code "86") (name "unconnected-(U4-PCM_DIN-Pad13)") (class "Default")
      (node (ref "U4") (pin "13") (pinfunction "PCM_DIN_13") (pintype "output"))
    )
    (net (code "87") (name "unconnected-(U4-PCM_DOUT-Pad14)") (class "Default")
      (node (ref "U4") (pin "14") (pinfunction "PCM_DOUT_14") (pintype "output"))
    )
    (net (code "88") (name "unconnected-(U4-PCM_SYNC-Pad12)") (class "Default")
      (node (ref "U4") (pin "12") (pinfunction "PCM_SYNC_12") (pintype "bidirectional"))
    )
    (net (code "89") (name "unconnected-(U4-RI-Pad4)") (class "Default")
      (node (ref "U4") (pin "4") (pinfunction "RI_4") (pintype "output"))
    )
    (net (code "90") (name "unconnected-(U4-RTS-Pad8)") (class "Default")
      (node (ref "U4") (pin "8") (pinfunction "RTS_8") (pintype "input"))
    )
    (net (code "91") (name "unconnected-(U4-SCL-Pad38)") (class "Default")
      (node (ref "U4") (pin "38") (pinfunction "SCL_38") (pintype "output"))
    )
    (net (code "92") (name "unconnected-(U4-SDA-Pad37)") (class "Default")
      (node (ref "U4") (pin "37") (pinfunction "SDA_37") (pintype "bidirectional"))
    )
    (net (code "93") (name "unconnected-(U4-SIM_DET-Pad34)") (class "Default")
      (node (ref "U4") (pin "34") (pinfunction "SIM_DET_34") (pintype "bidirectional"))
    )
    (net (code "94") (name "unconnected-(X1-PadID)") (class "Default")
      (node (ref "X1") (pin "ID") (pinfunction "ID_ID") (pintype "bidirectional"))
    )
    (net (code "95") (name "unconnected-(X4F-KL-Pad5)") (class "Default")
      (node (ref "X4") (pin "5") (pinfunction "KL_5") (pintype "passive"))
    )
    (net (code "96") (name "unconnected-(X4H-KL-Pad7)") (class "Default")
      (node (ref "X4") (pin "7") (pinfunction "KL_7") (pintype "passive"))
    )
  )
)
